# Cap.net
KiCad netlist of a schematic drawn in Altium Designer
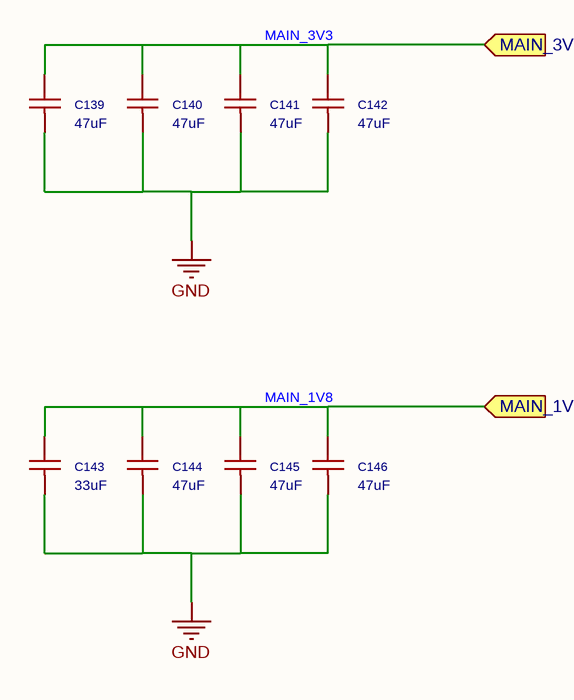
[diagram p0: Cap.schdoc]

(export (version "E")
  (design (tool "Eeschema 10.0.6"))
  (components
    (comp (ref "C139")
      (value "47uF")
      (footprint "C0603")
      (description "Capacitance:22nF Tolerance:±10% Tolerance:±10% Voltage Rating:50V Temperature Coefficient:X7R")
      (fields
        (field (name "MANUFACTURER PART") "CL10B223KB8NNNC")
        (field (name "MANUFACTURER") "SAMSUNG(三星)")
      )
      (libsource (lib "altium-import") (part "root_1_mirrored_CL10B223KB8NNNC_"))
    )
    (comp (ref "C140")
      (value "47uF")
      (footprint "C0603")
      (description "Capacitance:22nF Tolerance:±10% Tolerance:±10% Voltage Rating:50V Temperature Coefficient:X7R")
      (fields
        (field (name "MANUFACTURER PART") "CL10B223KB8NNNC")
        (field (name "MANUFACTURER") "SAMSUNG(三星)")
      )
      (libsource (lib "altium-import") (part "root_1_mirrored_CL10B223KB8NNNC_"))
    )
    (comp (ref "C141")
      (value "47uF")
      (footprint "C0603")
      (description "Capacitance:22nF Tolerance:±10% Tolerance:±10% Voltage Rating:50V Temperature Coefficient:X7R")
      (fields
        (field (name "MANUFACTURER PART") "CL10B223KB8NNNC")
        (field (name "MANUFACTURER") "SAMSUNG(三星)")
      )
      (libsource (lib "altium-import") (part "root_1_mirrored_CL10B223KB8NNNC_"))
    )
    (comp (ref "C142")
      (value "47uF")
      (footprint "C0603")
      (description "Capacitance:22nF Tolerance:±10% Tolerance:±10% Voltage Rating:50V Temperature Coefficient:X7R")
      (fields
        (field (name "MANUFACTURER PART") "CL10B223KB8NNNC")
        (field (name "MANUFACTURER") "SAMSUNG(三星)")
      )
      (libsource (lib "altium-import") (part "root_1_mirrored_CL10B223KB8NNNC_"))
    )
    (comp (ref "C143")
      (value "33uF")
      (footprint "C0603")
      (description "Capacitance:22nF Tolerance:±10% Tolerance:±10% Voltage Rating:50V Temperature Coefficient:X7R")
      (fields
        (field (name "MANUFACTURER PART") "CL10B223KB8NNNC")
        (field (name "MANUFACTURER") "SAMSUNG(三星)")
      )
      (libsource (lib "altium-import") (part "root_1_mirrored_CL10B223KB8NNNC_"))
    )
    (comp (ref "C144")
      (value "47uF")
      (footprint "C0603")
      (description "Capacitance:22nF Tolerance:±10% Tolerance:±10% Voltage Rating:50V Temperature Coefficient:X7R")
      (fields
        (field (name "MANUFACTURER PART") "CL10B223KB8NNNC")
        (field (name "MANUFACTURER") "SAMSUNG(三星)")
      )
      (libsource (lib "altium-import") (part "root_1_mirrored_CL10B223KB8NNNC_"))
    )
    (comp (ref "C145")
      (value "47uF")
      (footprint "C0603")
      (description "Capacitance:22nF Tolerance:±10% Tolerance:±10% Voltage Rating:50V Temperature Coefficient:X7R")
      (fields
        (field (name "MANUFACTURER PART") "CL10B223KB8NNNC")
        (field (name "MANUFACTURER") "SAMSUNG(三星)")
      )
      (libsource (lib "altium-import") (part "root_1_mirrored_CL10B223KB8NNNC_"))
    )
    (comp (ref "C146")
      (value "47uF")
      (footprint "C0603")
      (description "Capacitance:22nF Tolerance:±10% Tolerance:±10% Voltage Rating:50V Temperature Coefficient:X7R")
      (fields
        (field (name "MANUFACTURER PART") "CL10B223KB8NNNC")
        (field (name "MANUFACTURER") "SAMSUNG(三星)")
      )
      (libsource (lib "altium-import") (part "root_1_mirrored_CL10B223KB8NNNC_"))
    )
  )
  (nets
    (net (code "1") (name "/MAIN_1V8") (class "Default")
      (node (ref "C143") (pin "2") (pinfunction "2_2") (pintype "passive"))
      (node (ref "C144") (pin "2") (pinfunction "2_2") (pintype "passive"))
      (node (ref "C145") (pin "2") (pinfunction "2_2") (pintype "passive"))
      (node (ref "C146") (pin "2") (pinfunction "2_2") (pintype "passive"))
    )
    (net (code "2") (name "/MAIN_3V3") (class "Default")
      (node (ref "C139") (pin "2") (pinfunction "2_2") (pintype "passive"))
      (node (ref "C140") (pin "2") (pinfunction "2_2") (pintype "passive"))
      (node (ref "C141") (pin "2") (pinfunction "2_2") (pintype "passive"))
      (node (ref "C142") (pin "2") (pinfunction "2_2") (pintype "passive"))
    )
    (net (code "3") (name "GND") (class "Default")
      (node (ref "C139") (pin "1") (pinfunction "1_1") (pintype "passive"))
      (node (ref "C140") (pin "1") (pinfunction "1_1") (pintype "passive"))
      (node (ref "C141") (pin "1") (pinfunction "1_1") (pintype "passive"))
      (node (ref "C142") (pin "1") (pinfunction "1_1") (pintype "passive"))
      (node (ref "C143") (pin "1") (pinfunction "1_1") (pintype "passive"))
      (node (ref "C144") (pin "1") (pinfunction "1_1") (pintype "passive"))
      (node (ref "C145") (pin "1") (pinfunction "1_1") (pintype "passive"))
      (node (ref "C146") (pin "1") (pinfunction "1_1") (pintype "passive"))
    )
  )
)
